# PSU-schem.net
KiCad netlist of a schematic drawn in Altium Designer
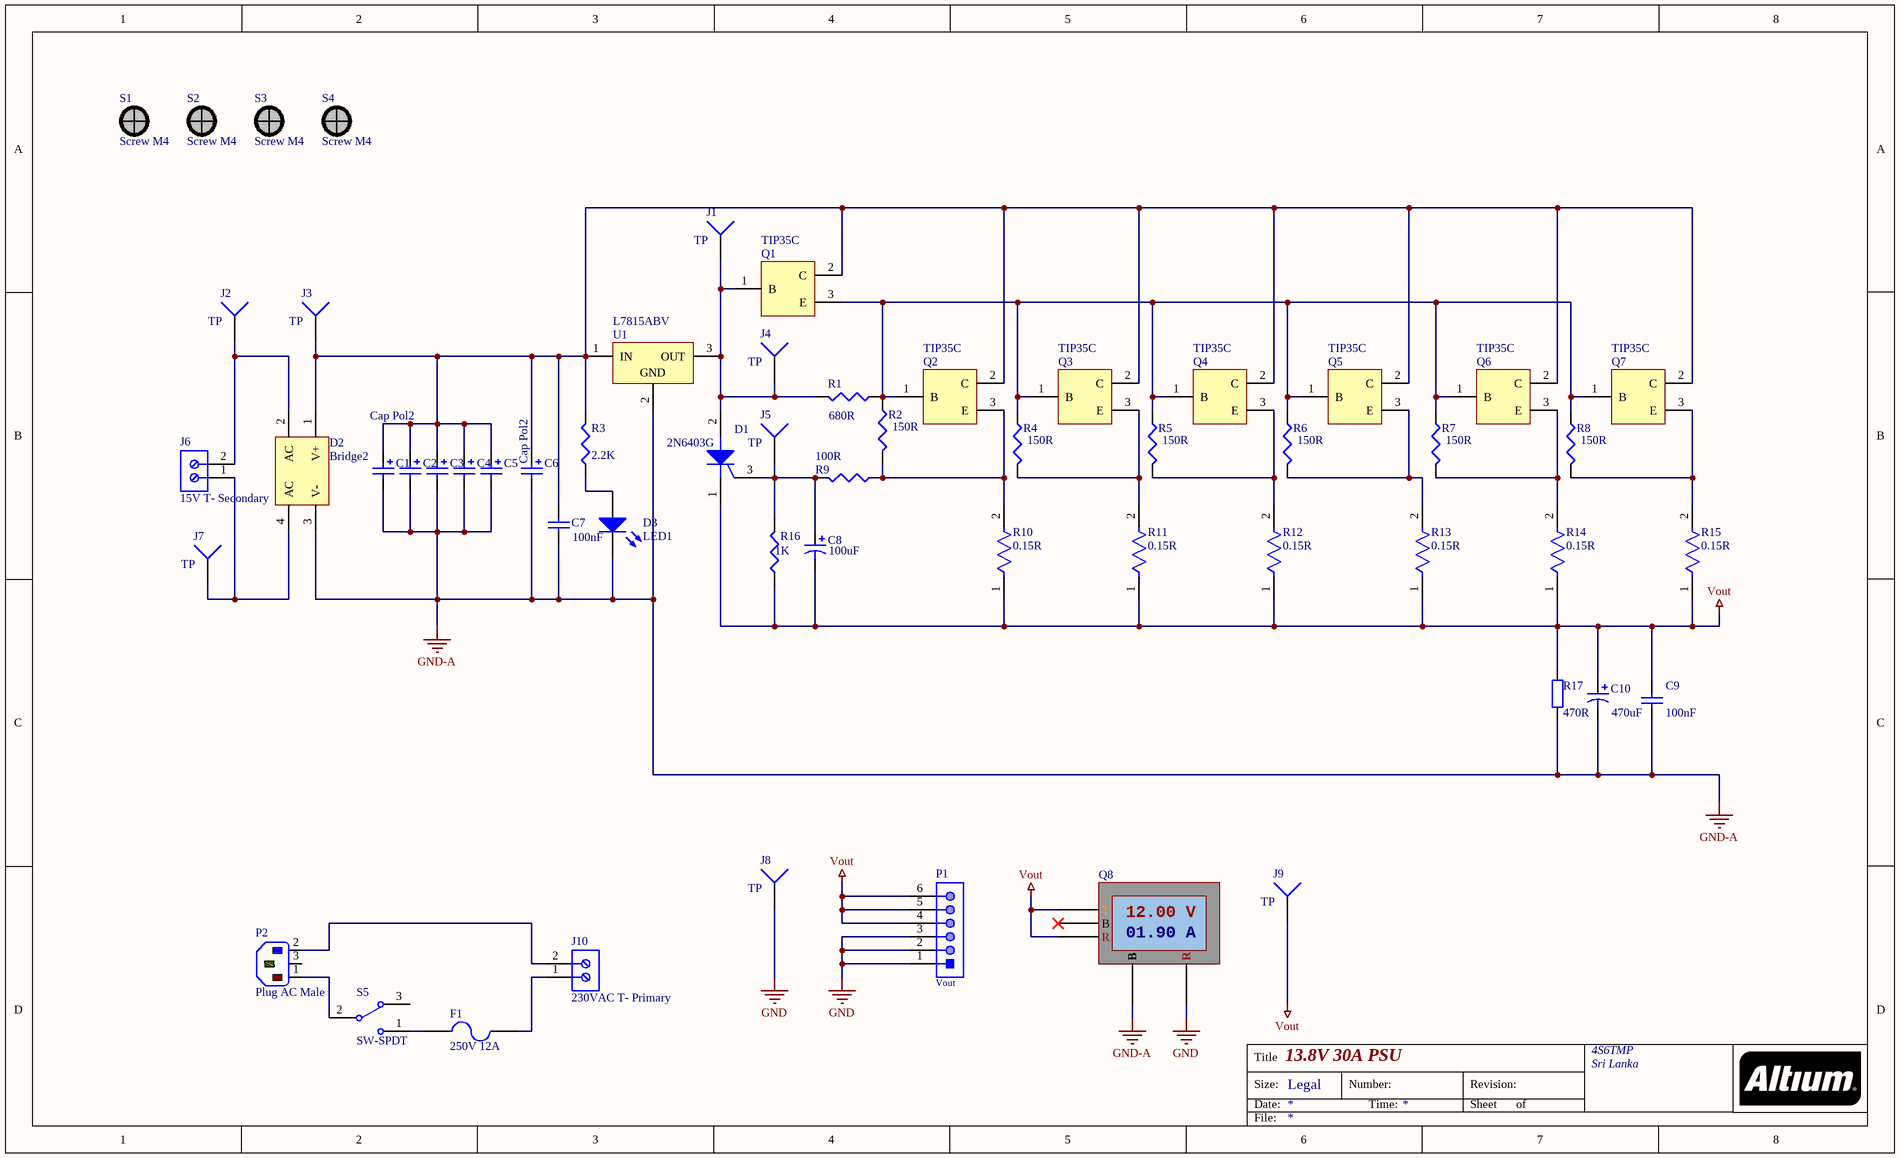
[diagram p0: PSU-schem.SchDoc]

(export (version "E")
  (design (tool "Eeschema 10.0.6"))
  (components
    (comp (ref "C1")
      (value "Cap Pol2")
      (footprint "CAP 20mm diameter, 7.6mm pitch")
      (description "Polarized Capacitor (Axial)")
      (fields (field (name "PUBLISHER") "Altium Limited"))
      (libsource (lib "Miscellaneous Devices") (part "Cap Pol2"))
    )
    (comp (ref "C2")
      (value "Cap Pol2")
      (footprint "CAP 20mm diameter, 7.6mm pitch")
      (description "Polarized Capacitor (Axial)")
      (fields (field (name "PUBLISHER") "Altium Limited"))
      (libsource (lib "Miscellaneous Devices") (part "Cap Pol2"))
    )
    (comp (ref "C3")
      (value "Cap Pol2")
      (footprint "CAP 20mm diameter, 7.6mm pitch")
      (description "Polarized Capacitor (Axial)")
      (fields (field (name "PUBLISHER") "Altium Limited"))
      (libsource (lib "Miscellaneous Devices") (part "Cap Pol2"))
    )
    (comp (ref "C4")
      (value "Cap Pol2")
      (footprint "CAP 20mm diameter, 7.6mm pitch")
      (description "Polarized Capacitor (Axial)")
      (fields (field (name "PUBLISHER") "Altium Limited"))
      (libsource (lib "Miscellaneous Devices") (part "Cap Pol2"))
    )
    (comp (ref "C5")
      (value "Cap Pol2")
      (footprint "CAP 20mm diameter, 7.6mm pitch")
      (description "Polarized Capacitor (Axial)")
      (fields (field (name "PUBLISHER") "Altium Limited"))
      (libsource (lib "Miscellaneous Devices") (part "Cap Pol2"))
    )
    (comp (ref "C6")
      (value "Cap Pol2")
      (footprint "CAP 20mm diameter, 7.6mm pitch")
      (description "Polarized Capacitor (Axial)")
      (fields (field (name "PUBLISHER") "Altium Limited"))
      (libsource (lib "Miscellaneous Devices") (part "Cap Pol2"))
    )
    (comp (ref "C7")
      (value "100nF")
      (footprint "C 0603 / 1608")
      (description "Capacitor")
      (fields (field (name "Comment") "Cap") (field (name "PUBLISHER") "Altium Limited"))
      (libsource (lib "Miscellaneous Devices") (part "Cap"))
    )
    (comp (ref "C8")
      (value "100uF")
      (footprint "CAPR5-4X5")
      (description "Polarized Capacitor (Surface Mount)")
      (fields (field (name "Comment") "Cap Pol3") (field (name "PUBLISHER") "Altium Limited"))
      (libsource (lib "Miscellaneous Devices") (part "Cap Pol3"))
    )
    (comp (ref "C9")
      (value "100nF")
      (footprint "C 0603 / 1608")
      (description "Capacitor")
      (fields (field (name "Comment") "Cap") (field (name "PUBLISHER") "Altium Limited"))
      (libsource (lib "Miscellaneous Devices") (part "Cap"))
    )
    (comp (ref "C10")
      (value "470uF")
      (footprint "RAD-0.3")
      (description "Polarized Capacitor (Surface Mount)")
      (fields (field (name "Comment") "Cap Pol3") (field (name "PUBLISHER") "Altium Limited"))
      (libsource (lib "Miscellaneous Devices") (part "Cap Pol3"))
    )
    (comp (ref "D1")
      (value "2N6403G")
      (footprint "ONSC-TO-220-3-221A-07")
      (description "Silicon Controlled Rectifier, Reverse Blocking Thyristor, 3-Pin TO-220, Pb-Free, Bulk Box")
      (fields (field (name "MANUFACTURER") "On Semiconductor"))
      (libsource (lib "Altium Content Vault") (part "ONSC-SCR-K1A2G3-3"))
    )
    (comp (ref "D2")
      (value "Bridge2")
      (footprint "D-46_6A")
      (description "Diode Bridge")
      (fields (field (name "PUBLISHER") "Altium Limited"))
      (libsource (lib "Miscellaneous Devices") (part "Bridge2"))
    )
    (comp (ref "D3")
      (value "LED1")
      (footprint "LED-1")
      (description "Typical RED GaAs LED")
      (fields (field (name "PUBLISHER") "Altium Limited"))
      (libsource (lib "Miscellaneous Devices") (part "LED1"))
    )
    (comp (ref "F1")
      (value "250V 12A")
      (footprint "PIN-W2/E2.8")
      (description "Fuse")
      (fields (field (name "PUBLISHER") "Altium Limited"))
      (libsource (lib "Miscellaneous Devices") (part "Fuse 2"))
    )
    (comp (ref "J1")
      (value "TP")
      (footprint "PIN1")
      (description "Socket")
      (fields (field (name "PUBLISHER") "Altium Limited"))
      (libsource (lib "Miscellaneous Connectors") (part "Socket"))
    )
    (comp (ref "J2")
      (value "TP")
      (footprint "PIN1")
      (description "Socket")
      (fields (field (name "PUBLISHER") "Altium Limited"))
      (libsource (lib "Miscellaneous Connectors") (part "Socket"))
    )
    (comp (ref "J3")
      (value "TP")
      (footprint "PIN1")
      (description "Socket")
      (fields (field (name "PUBLISHER") "Altium Limited"))
      (libsource (lib "Miscellaneous Connectors") (part "Socket"))
    )
    (comp (ref "J4")
      (value "TP")
      (footprint "PIN1")
      (description "Socket")
      (fields (field (name "PUBLISHER") "Altium Limited"))
      (libsource (lib "Miscellaneous Connectors") (part "Socket"))
    )
    (comp (ref "J5")
      (value "TP")
      (footprint "PIN1")
      (description "Socket")
      (fields (field (name "PUBLISHER") "Altium Limited"))
      (libsource (lib "Miscellaneous Connectors") (part "Socket"))
    )
    (comp (ref "J6")
      (value "15V T- Secondary")
      (footprint "TECO-282836-2_V")
      (description "Female Header, Pitch 5 mm, 1 x 2 Position, Height 10 mm, Tail Length 3.5 mm, Rohs, Bulk")
      (fields (field (name "VOLTAGE") "300V") (field (name "MANUFACTURER") "TE Connectivity"))
      (libsource (lib "Altium Content Vault") (part "CN-1P-F-TB2"))
    )
    (comp (ref "J7")
      (value "TP")
      (footprint "PIN1")
      (description "Socket")
      (fields (field (name "PUBLISHER") "Altium Limited"))
      (libsource (lib "Miscellaneous Connectors") (part "Socket"))
    )
    (comp (ref "J8")
      (value "TP")
      (footprint "PIN1")
      (description "Socket")
      (fields (field (name "PUBLISHER") "Altium Limited"))
      (libsource (lib "Miscellaneous Connectors") (part "Socket"))
    )
    (comp (ref "J9")
      (value "TP")
      (footprint "PIN1")
      (description "Socket")
      (fields (field (name "PUBLISHER") "Altium Limited"))
      (libsource (lib "Miscellaneous Connectors") (part "Socket"))
    )
    (comp (ref "J10")
      (value "230VAC T- Primary")
      (footprint "TECO-282836-2_V")
      (description "Female Header, Pitch 5 mm, 1 x 2 Position, Height 10 mm, Tail Length 3.5 mm, Rohs, Bulk")
      (fields (field (name "VOLTAGE") "300V") (field (name "MANUFACTURER") "TE Connectivity"))
      (libsource (lib "Altium Content Vault") (part "CN-1P-F-TB2"))
    )
    (comp (ref "P1")
      (value "Vout")
      (footprint "691312710006")
      (description "Serie 3127 - 5.00mm Open Horizontal PCB Header WR-TBL, 6 pin")
      (fields
        (field (name "PART NUMBER") "691312710006")
        (field (name "MANUFACTURER") "Wurth Elektronik")
        (field (name "PUBLISHER") "WurthElektronik")
      )
      (libsource (lib "Altium Content Vault") (part "WE-CN-1P-M-R6"))
    )
    (comp (ref "P2")
      (value "Plug AC Male")
      (footprint "Screw terminal 3-pin 7.62mm")
      (description "IEC Mains Power Inlet, EN60 320-1 C14 Class I Cold Condition, PC Flange Rear Mount, Chassis Plug")
      (fields (field (name "PUBLISHER") "Altium Limited"))
      (libsource (lib "Miscellaneous Connectors") (part "Plug AC Male"))
    )
    (comp (ref "Q1")
      (value "TIP35C")
      (footprint "ONSC-SOT-93_TO-218-3-340D-02")
      (description "Complementary Silicon High-Power Transistor, 3-Pin SOT-93, Tube")
      (fields (field (name "MANUFACTURER") "On Semiconductor"))
      (libsource (lib "Altium Content Vault") (part "ONSC-NPN-B1C2E3-3_B"))
    )
    (comp (ref "Q2")
      (value "TIP35C")
      (footprint "ONSC-SOT-93_TO-218-3-340D-02")
      (description "Complementary Silicon High-Power Transistor, 3-Pin SOT-93, Tube")
      (fields (field (name "MANUFACTURER") "On Semiconductor"))
      (libsource (lib "Altium Content Vault") (part "ONSC-NPN-B1C2E3-3_B"))
    )
    (comp (ref "Q3")
      (value "TIP35C")
      (footprint "ONSC-SOT-93_TO-218-3-340D-02")
      (description "Complementary Silicon High-Power Transistor, 3-Pin SOT-93, Tube")
      (fields (field (name "MANUFACTURER") "On Semiconductor"))
      (libsource (lib "Altium Content Vault") (part "ONSC-NPN-B1C2E3-3_B"))
    )
    (comp (ref "Q4")
      (value "TIP35C")
      (footprint "ONSC-SOT-93_TO-218-3-340D-02")
      (description "Complementary Silicon High-Power Transistor, 3-Pin SOT-93, Tube")
      (fields (field (name "MANUFACTURER") "On Semiconductor"))
      (libsource (lib "Altium Content Vault") (part "ONSC-NPN-B1C2E3-3_B"))
    )
    (comp (ref "Q5")
      (value "TIP35C")
      (footprint "ONSC-SOT-93_TO-218-3-340D-02")
      (description "Complementary Silicon High-Power Transistor, 3-Pin SOT-93, Tube")
      (fields (field (name "MANUFACTURER") "On Semiconductor"))
      (libsource (lib "Altium Content Vault") (part "ONSC-NPN-B1C2E3-3_B"))
    )
    (comp (ref "Q6")
      (value "TIP35C")
      (footprint "ONSC-SOT-93_TO-218-3-340D-02")
      (description "Complementary Silicon High-Power Transistor, 3-Pin SOT-93, Tube")
      (fields (field (name "MANUFACTURER") "On Semiconductor"))
      (libsource (lib "Altium Content Vault") (part "ONSC-NPN-B1C2E3-3_B"))
    )
    (comp (ref "Q7")
      (value "TIP35C")
      (footprint "ONSC-SOT-93_TO-218-3-340D-02")
      (description "Complementary Silicon High-Power Transistor, 3-Pin SOT-93, Tube")
      (fields (field (name "MANUFACTURER") "On Semiconductor"))
      (libsource (lib "Altium Content Vault") (part "ONSC-NPN-B1C2E3-3_B"))
    )
    (comp (ref "Q8")
      (value "VA_Meter")
      (footprint "VA_Meter")
      (description "Digital V/A Meter")
      (libsource (lib "digital-v-a-meter") (part "VA_Meter"))
    )
    (comp (ref "R1")
      (value "680R")
      (footprint "3-0603")
      (description "Resistor")
      (fields
        (field (name "MANUFACTURER") "Uniroyal")
        (field (name "MANUFACTURER PART NUMBER") "0603WAJ0681T5E")
        (field (name "PUBLISHER") "Altium Limited")
      )
      (libsource (lib "Miscellaneous Devices") (part "Res3"))
    )
    (comp (ref "R2")
      (value "150R")
      (footprint "3-0603")
      (description "Resistor")
      (fields (field (name "Comment") "Res3") (field (name "PUBLISHER") "Altium Limited"))
      (libsource (lib "Miscellaneous Devices") (part "Res3"))
    )
    (comp (ref "R3")
      (value "2.2K")
      (footprint "3-0603")
      (description "Resistor")
      (fields (field (name "Comment") "Res3") (field (name "PUBLISHER") "Altium Limited"))
      (libsource (lib "Miscellaneous Devices") (part "Res3"))
    )
    (comp (ref "R4")
      (value "150R")
      (footprint "3-0603")
      (description "Resistor")
      (fields (field (name "Comment") "Res3") (field (name "PUBLISHER") "Altium Limited"))
      (libsource (lib "Miscellaneous Devices") (part "Res3"))
    )
    (comp (ref "R5")
      (value "150R")
      (footprint "3-0603")
      (description "Resistor")
      (fields (field (name "Comment") "Res3") (field (name "PUBLISHER") "Altium Limited"))
      (libsource (lib "Miscellaneous Devices") (part "Res3"))
    )
    (comp (ref "R6")
      (value "150R")
      (footprint "3-0603")
      (description "Resistor")
      (fields (field (name "Comment") "Res3") (field (name "PUBLISHER") "Altium Limited"))
      (libsource (lib "Miscellaneous Devices") (part "Res3"))
    )
    (comp (ref "R7")
      (value "150R")
      (footprint "3-0603")
      (description "Resistor")
      (fields (field (name "Comment") "Res3") (field (name "PUBLISHER") "Altium Limited"))
      (libsource (lib "Miscellaneous Devices") (part "Res3"))
    )
    (comp (ref "R8")
      (value "150R")
      (footprint "3-0603")
      (description "Resistor")
      (fields (field (name "Comment") "Res3") (field (name "PUBLISHER") "Altium Limited"))
      (libsource (lib "Miscellaneous Devices") (part "Res3"))
    )
    (comp (ref "R9")
      (value "100R")
      (footprint "3-0603")
      (description "Resistor")
      (fields (field (name "Comment") "Res3") (field (name "PUBLISHER") "Altium Limited"))
      (libsource (lib "Miscellaneous Devices") (part "Res3"))
    )
    (comp (ref "R10")
      (value "0.15R")
      (footprint "FP-AC05000003909JAC00-0")
      (description "RES 0.15 OHM 5W 5%")
      (libsource (lib "Altium Content Vault") (part "1029c3af85768c4190bb7ad29bc67b5"))
    )
    (comp (ref "R11")
      (value "0.15R")
      (footprint "FP-AC05000003909JAC00-0")
      (description "RES 0.15 OHM 5W 5%")
      (libsource (lib "Altium Content Vault") (part "1029c3af85768c4190bb7ad29bc67b5"))
    )
    (comp (ref "R12")
      (value "0.15R")
      (footprint "FP-AC05000003909JAC00-0")
      (description "RES 0.15 OHM 5W 5%")
      (libsource (lib "Altium Content Vault") (part "1029c3af85768c4190bb7ad29bc67b5"))
    )
    (comp (ref "R13")
      (value "0.15R")
      (footprint "FP-AC05000003909JAC00-0")
      (description "RES 0.15 OHM 5W 5%")
      (libsource (lib "Altium Content Vault") (part "1029c3af85768c4190bb7ad29bc67b5"))
    )
    (comp (ref "R14")
      (value "0.15R")
      (footprint "FP-AC05000003909JAC00-0")
      (description "RES 0.15 OHM 5W 5%")
      (libsource (lib "Altium Content Vault") (part "1029c3af85768c4190bb7ad29bc67b5"))
    )
    (comp (ref "R15")
      (value "0.15R")
      (footprint "FP-AC05000003909JAC00-0")
      (description "RES 0.15 OHM 5W 5%")
      (libsource (lib "Altium Content Vault") (part "1029c3af85768c4190bb7ad29bc67b5"))
    )
    (comp (ref "R16")
      (value "1K")
      (footprint "3-0603")
      (description "Resistor")
      (fields (field (name "Comment") "Res3") (field (name "PUBLISHER") "Altium Limited"))
      (libsource (lib "Miscellaneous Devices") (part "Res3"))
    )
    (comp (ref "R17")
      (value "470R")
      (footprint "AXIAL-0.4")
      (description "Resistor")
      (fields (field (name "Comment") "Res2") (field (name "PUBLISHER") "Altium Limited"))
      (libsource (lib "Miscellaneous Devices") (part "Res2"))
    )
    (comp (ref "S1")
      (value "Screw M4")
      (footprint "Screw M4")
      (libsource (lib "Mechanical") (part "Screw M4"))
    )
    (comp (ref "S2")
      (value "Screw M4")
      (footprint "Screw M4")
      (libsource (lib "Mechanical") (part "Screw M4"))
    )
    (comp (ref "S3")
      (value "Screw M4")
      (footprint "Screw M4")
      (libsource (lib "Mechanical") (part "Screw M4"))
    )
    (comp (ref "S4")
      (value "Screw M4")
      (footprint "Screw M4")
      (libsource (lib "Mechanical") (part "Screw M4"))
    )
    (comp (ref "S5")
      (value "SW-SPDT")
      (footprint "TL36WW15050")
      (description "SPDT Subminiature Toggle Switch, Right Angle Mounting, Vertical Actuation")
      (fields (field (name "PUBLISHER") "Altium Limited"))
      (libsource (lib "Miscellaneous Devices") (part "SW-SPDT"))
    )
    (comp (ref "U1")
      (value "L7815ABV")
      (footprint "TO220")
      (description "Positive Voltage Regulator, 15V, 3-Pin TO-220")
      (libsource (lib "Altium Content Vault") (part "PM-REG-L4940-SIL3"))
    )
  )
  (nets
    (net (code "1") (name "GND") (class "Default")
      (node (ref "J8") (pin "1") (pinfunction "1_1") (pintype "passive"))
      (node (ref "P1") (pin "1") (pinfunction "1_1") (pintype "passive"))
      (node (ref "P1") (pin "2") (pinfunction "2_2") (pintype "passive"))
      (node (ref "P1") (pin "3") (pinfunction "3_3") (pintype "passive"))
      (node (ref "Q8") (pin "5") (pinfunction "R_5") (pintype "passive"))
    )
    (net (code "2") (name "GND-A") (class "Default")
      (node (ref "C1") (pin "2") (pinfunction "2_2") (pintype "passive"))
      (node (ref "C10") (pin "2") (pinfunction "2_2") (pintype "passive"))
      (node (ref "C2") (pin "2") (pinfunction "2_2") (pintype "passive"))
      (node (ref "C3") (pin "2") (pinfunction "2_2") (pintype "passive"))
      (node (ref "C4") (pin "2") (pinfunction "2_2") (pintype "passive"))
      (node (ref "C5") (pin "2") (pinfunction "2_2") (pintype "passive"))
      (node (ref "C6") (pin "2") (pinfunction "2_2") (pintype "passive"))
      (node (ref "C7") (pin "1") (pinfunction "1_1") (pintype "passive"))
      (node (ref "C9") (pin "1") (pinfunction "1_1") (pintype "passive"))
      (node (ref "D2") (pin "3") (pinfunction "V-_3") (pintype "passive"))
      (node (ref "D3") (pin "2") (pinfunction "K_2") (pintype "passive"))
      (node (ref "Q8") (pin "4") (pinfunction "B_4") (pintype "passive"))
      (node (ref "R17") (pin "1") (pinfunction "1_1") (pintype "passive"))
      (node (ref "U1") (pin "2") (pinfunction "GND_2") (pintype "power_in"))
    )
    (net (code "3") (name "Net-(D1-A)") (class "Default")
      (node (ref "D1") (pin "2") (pinfunction "A_2") (pintype "passive"))
      (node (ref "J1") (pin "1") (pinfunction "1_1") (pintype "passive"))
      (node (ref "J4") (pin "1") (pinfunction "1_1") (pintype "passive"))
      (node (ref "Q1") (pin "1") (pinfunction "B_1") (pintype "passive"))
      (node (ref "R1") (pin "2") (pinfunction "2_2") (pintype "passive"))
      (node (ref "U1") (pin "3") (pinfunction "OUT_3") (pintype "power_in"))
    )
    (net (code "4") (name "Net-(D1-G)") (class "Default")
      (node (ref "C8") (pin "1") (pinfunction "1_1") (pintype "passive"))
      (node (ref "D1") (pin "3") (pinfunction "G_3") (pintype "passive"))
      (node (ref "J5") (pin "1") (pinfunction "1_1") (pintype "passive"))
      (node (ref "R16") (pin "2") (pinfunction "2_2") (pintype "passive"))
      (node (ref "R9") (pin "2") (pinfunction "2_2") (pintype "passive"))
    )
    (net (code "5") (name "Net-(D2-AC-Pad2)") (class "Default")
      (node (ref "D2") (pin "2") (pinfunction "AC_2") (pintype "passive"))
      (node (ref "J2") (pin "1") (pinfunction "1_1") (pintype "passive"))
      (node (ref "J6") (pin "2") (pinfunction "2_2") (pintype "passive"))
    )
    (net (code "6") (name "Net-(D2-AC-Pad4)") (class "Default")
      (node (ref "D2") (pin "4") (pinfunction "AC_4") (pintype "passive"))
      (node (ref "J6") (pin "1") (pinfunction "1_1") (pintype "passive"))
      (node (ref "J7") (pin "1") (pinfunction "1_1") (pintype "passive"))
    )
    (net (code "7") (name "Net-(D2-V+)") (class "Default")
      (node (ref "C1") (pin "1") (pinfunction "1_1") (pintype "passive"))
      (node (ref "C2") (pin "1") (pinfunction "1_1") (pintype "passive"))
      (node (ref "C3") (pin "1") (pinfunction "1_1") (pintype "passive"))
      (node (ref "C4") (pin "1") (pinfunction "1_1") (pintype "passive"))
      (node (ref "C5") (pin "1") (pinfunction "1_1") (pintype "passive"))
      (node (ref "C6") (pin "1") (pinfunction "1_1") (pintype "passive"))
      (node (ref "C7") (pin "2") (pinfunction "2_2") (pintype "passive"))
      (node (ref "D2") (pin "1") (pinfunction "V+_1") (pintype "passive"))
      (node (ref "J3") (pin "1") (pinfunction "1_1") (pintype "passive"))
      (node (ref "Q1") (pin "2") (pinfunction "C_2") (pintype "passive"))
      (node (ref "Q2") (pin "2") (pinfunction "C_2") (pintype "passive"))
      (node (ref "Q3") (pin "2") (pinfunction "C_2") (pintype "passive"))
      (node (ref "Q4") (pin "2") (pinfunction "C_2") (pintype "passive"))
      (node (ref "Q5") (pin "2") (pinfunction "C_2") (pintype "passive"))
      (node (ref "Q6") (pin "2") (pinfunction "C_2") (pintype "passive"))
      (node (ref "Q7") (pin "2") (pinfunction "C_2") (pintype "passive"))
      (node (ref "R3") (pin "2") (pinfunction "2_2") (pintype "passive"))
      (node (ref "U1") (pin "1") (pinfunction "IN_1") (pintype "power_in"))
    )
    (net (code "8") (name "Net-(D3-A)") (class "Default")
      (node (ref "D3") (pin "1") (pinfunction "A_1") (pintype "passive"))
      (node (ref "R3") (pin "1") (pinfunction "1_1") (pintype "passive"))
    )
    (net (code "9") (name "Net-(F1-Pad1)") (class "Default")
      (node (ref "F1") (pin "1") (pinfunction "1_1") (pintype "passive"))
      (node (ref "S5") (pin "1") (pinfunction "1_1") (pintype "passive"))
    )
    (net (code "10") (name "Net-(F1-Pad2)") (class "Default")
      (node (ref "F1") (pin "2") (pinfunction "2_2") (pintype "passive"))
      (node (ref "J10") (pin "1") (pinfunction "1_1") (pintype "passive"))
    )
    (net (code "11") (name "Net-(P2-L)") (class "Default")
      (node (ref "P2") (pin "1") (pinfunction "L_1") (pintype "power_in"))
      (node (ref "S5") (pin "2") (pinfunction "2_2") (pintype "passive"))
    )
    (net (code "12") (name "Net-(P2-N)") (class "Default")
      (node (ref "J10") (pin "2") (pinfunction "2_2") (pintype "passive"))
      (node (ref "P2") (pin "2") (pinfunction "N_2") (pintype "power_in"))
    )
    (net (code "13") (name "Net-(Q1-E)") (class "Default")
      (node (ref "Q1") (pin "3") (pinfunction "E_3") (pintype "passive"))
      (node (ref "Q2") (pin "1") (pinfunction "B_1") (pintype "passive"))
      (node (ref "Q3") (pin "1") (pinfunction "B_1") (pintype "passive"))
      (node (ref "Q4") (pin "1") (pinfunction "B_1") (pintype "passive"))
      (node (ref "Q5") (pin "1") (pinfunction "B_1") (pintype "passive"))
      (node (ref "Q6") (pin "1") (pinfunction "B_1") (pintype "passive"))
      (node (ref "Q7") (pin "1") (pinfunction "B_1") (pintype "passive"))
      (node (ref "R1") (pin "1") (pinfunction "1_1") (pintype "passive"))
      (node (ref "R2") (pin "1") (pinfunction "1_1") (pintype "passive"))
      (node (ref "R4") (pin "1") (pinfunction "1_1") (pintype "passive"))
      (node (ref "R5") (pin "1") (pinfunction "1_1") (pintype "passive"))
      (node (ref "R6") (pin "1") (pinfunction "1_1") (pintype "passive"))
      (node (ref "R7") (pin "1") (pinfunction "1_1") (pintype "passive"))
      (node (ref "R8") (pin "1") (pinfunction "1_1") (pintype "passive"))
    )
    (net (code "14") (name "Net-(Q2-E)") (class "Default")
      (node (ref "Q2") (pin "3") (pinfunction "E_3") (pintype "passive"))
      (node (ref "R10") (pin "2") (pinfunction "2_2") (pintype "passive"))
      (node (ref "R2") (pin "2") (pinfunction "2_2") (pintype "passive"))
      (node (ref "R9") (pin "1") (pinfunction "1_1") (pintype "passive"))
    )
    (net (code "15") (name "Net-(Q3-E)") (class "Default")
      (node (ref "Q3") (pin "3") (pinfunction "E_3") (pintype "passive"))
      (node (ref "R11") (pin "2") (pinfunction "2_2") (pintype "passive"))
      (node (ref "R4") (pin "2") (pinfunction "2_2") (pintype "passive"))
    )
    (net (code "16") (name "Net-(Q4-E)") (class "Default")
      (node (ref "Q4") (pin "3") (pinfunction "E_3") (pintype "passive"))
      (node (ref "R12") (pin "2") (pinfunction "2_2") (pintype "passive"))
      (node (ref "R5") (pin "2") (pinfunction "2_2") (pintype "passive"))
    )
    (net (code "17") (name "Net-(Q5-E)") (class "Default")
      (node (ref "Q5") (pin "3") (pinfunction "E_3") (pintype "passive"))
      (node (ref "R13") (pin "2") (pinfunction "2_2") (pintype "passive"))
      (node (ref "R6") (pin "2") (pinfunction "2_2") (pintype "passive"))
    )
    (net (code "18") (name "Net-(Q6-E)") (class "Default")
      (node (ref "Q6") (pin "3") (pinfunction "E_3") (pintype "passive"))
      (node (ref "R14") (pin "2") (pinfunction "2_2") (pintype "passive"))
      (node (ref "R7") (pin "2") (pinfunction "2_2") (pintype "passive"))
    )
    (net (code "19") (name "Net-(Q7-E)") (class "Default")
      (node (ref "Q7") (pin "3") (pinfunction "E_3") (pintype "passive"))
      (node (ref "R15") (pin "2") (pinfunction "2_2") (pintype "passive"))
      (node (ref "R8") (pin "2") (pinfunction "2_2") (pintype "passive"))
    )
    (net (code "20") (name "Vout") (class "Default")
      (node (ref "C10") (pin "1") (pinfunction "1_1") (pintype "passive"))
      (node (ref "C8") (pin "2") (pinfunction "2_2") (pintype "passive"))
      (node (ref "C9") (pin "2") (pinfunction "2_2") (pintype "passive"))
      (node (ref "D1") (pin "1") (pinfunction "K_1") (pintype "passive"))
      (node (ref "J9") (pin "1") (pinfunction "1_1") (pintype "passive"))
      (node (ref "P1") (pin "4") (pinfunction "4_4") (pintype "passive"))
      (node (ref "P1") (pin "5") (pinfunction "5_5") (pintype "passive"))
      (node (ref "P1") (pin "6") (pinfunction "6_6") (pintype "passive"))
      (node (ref "Q8") (pin "1") (pinfunction "Y_1") (pintype "power_in"))
      (node (ref "Q8") (pin "3") (pinfunction "R_3") (pintype "power_in"))
      (node (ref "R10") (pin "1") (pinfunction "1_1") (pintype "passive"))
      (node (ref "R11") (pin "1") (pinfunction "1_1") (pintype "passive"))
      (node (ref "R12") (pin "1") (pinfunction "1_1") (pintype "passive"))
      (node (ref "R13") (pin "1") (pinfunction "1_1") (pintype "passive"))
      (node (ref "R14") (pin "1") (pinfunction "1_1") (pintype "passive"))
      (node (ref "R15") (pin "1") (pinfunction "1_1") (pintype "passive"))
      (node (ref "R16") (pin "1") (pinfunction "1_1") (pintype "passive"))
      (node (ref "R17") (pin "2") (pinfunction "2_2") (pintype "passive"))
    )
    (net (code "21") (name "unconnected-(P2-E-Pad3)") (class "Default")
      (node (ref "P2") (pin "3") (pinfunction "E_3") (pintype "power_in"))
    )
    (net (code "22") (name "unconnected-(Q8-B-Pad2)") (class "Default")
      (node (ref "Q8") (pin "2") (pinfunction "B_2") (pintype "power_in+no_connect"))
    )
    (net (code "23") (name "unconnected-(S5-Pad3)") (class "Default")
      (node (ref "S5") (pin "3") (pinfunction "3_3") (pintype "passive"))
    )
  )
)
